# 10_FLASH_BOOT.net
KiCad netlist of a schematic drawn in Altium Designer
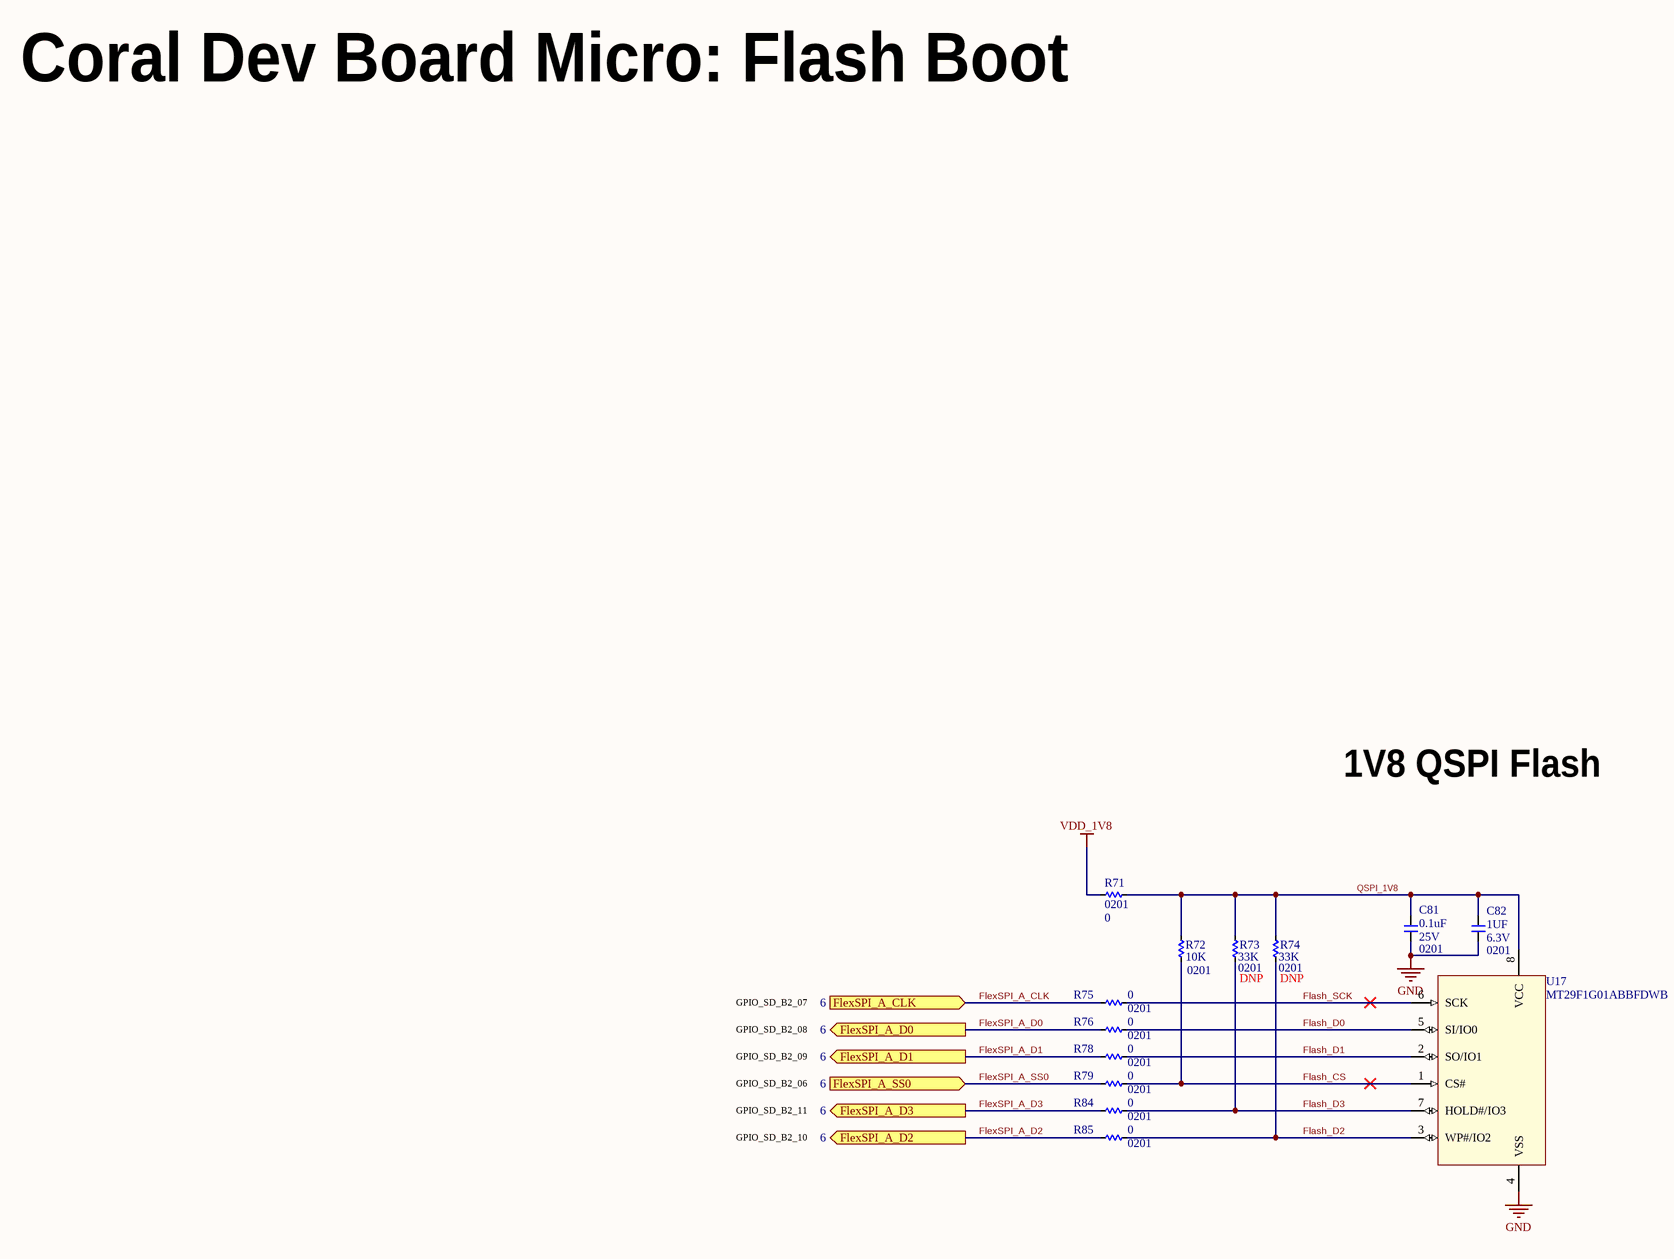
[diagram p0: 10 FLASH_BOOT.SchDoc]

(export (version "E")
  (design (tool "Eeschema 10.0.6"))
  (components
    (comp (ref "C81")
      (value "0.1uF")
      (footprint "C0201Y")
      (description "CAP, CER, X5R, 0.1uF, 25V, 20%, 0201, 0.33mm T")
      (fields
        (field (name "MFG") "MURATA")
        (field (name "PACKAGE") "0201")
        (field (name "VOLTAGE") "25V")
        (field (name "TOLERANCE") "20%")
      )
      (libsource (lib "AltiumReleaseLibDB") (part "__Template_Cap"))
    )
    (comp (ref "C82")
      (value "1UF")
      (footprint "C0201_H0.39MM")
      (description "CAP, CER, X6S, 1uF, 20%, 6.3V, 0201, 0.39mm")
      (fields
        (field (name "MFG") "MURATA")
        (field (name "PACKAGE") "0201")
        (field (name "VOLTAGE") "6.3V")
        (field (name "TOLERANCE") "20%")
      )
      (libsource (lib "AltiumReleaseLibDB") (part "__Template_Cap"))
    )
    (comp (ref "R71")
      (value "0")
      (footprint "R0201")
      (description "RES, 0.0, 1/20W, 0201")
      (fields (field (name "MFG") "PANASONIC") (field (name "PACKAGE") "0201") (field (name "POWER") "1/20W"))
      (libsource (lib "AltiumReleaseLibDB") (part "__Template_Resistor"))
    )
    (comp (ref "R72")
      (value "10K")
      (footprint "R0201")
      (description "RES, 10K, 1%, 1/20W, 0201")
      (fields (field (name "MFG") "YAGEO") (field (name "PACKAGE") "0201") (field (name "POWER") "1/20W"))
      (libsource (lib "AltiumReleaseLibDB") (part "__Template_Resistor"))
    )
    (comp (ref "R73")
      (value "33K")
      (footprint "R0201")
      (description "RES, 33K, 1%, 1/20W, 0201")
      (fields
        (field (name "MFG") "YAGEO")
        (field (name "PACKAGE") "0201")
        (field (name "POWER") "1/20W")
        (field (name "DNP") "DNP")
      )
      (libsource (lib "AltiumReleaseLibDB") (part "__Template_Resistor"))
    )
    (comp (ref "R74")
      (value "33K")
      (footprint "R0201")
      (description "RES, 33K, 1%, 1/20W, 0201")
      (fields
        (field (name "MFG") "YAGEO")
        (field (name "PACKAGE") "0201")
        (field (name "POWER") "1/20W")
        (field (name "DNP") "DNP")
      )
      (libsource (lib "AltiumReleaseLibDB") (part "__Template_Resistor"))
    )
    (comp (ref "R75")
      (value "0")
      (footprint "R0201")
      (description "RES, 0.0, 1/20W, 0201")
      (fields (field (name "MFG") "PANASONIC") (field (name "PACKAGE") "0201") (field (name "POWER") "1/20W"))
      (libsource (lib "AltiumReleaseLibDB") (part "__Template_Resistor"))
    )
    (comp (ref "R76")
      (value "0")
      (footprint "R0201")
      (description "RES, 0.0, 1/20W, 0201")
      (fields (field (name "MFG") "PANASONIC") (field (name "PACKAGE") "0201") (field (name "POWER") "1/20W"))
      (libsource (lib "AltiumReleaseLibDB") (part "__Template_Resistor"))
    )
    (comp (ref "R78")
      (value "0")
      (footprint "R0201")
      (description "RES, 0.0, 1/20W, 0201")
      (fields (field (name "MFG") "PANASONIC") (field (name "PACKAGE") "0201") (field (name "POWER") "1/20W"))
      (libsource (lib "AltiumReleaseLibDB") (part "__Template_Resistor"))
    )
    (comp (ref "R79")
      (value "0")
      (footprint "R0201")
      (description "RES, 0.0, 1/20W, 0201")
      (fields (field (name "MFG") "PANASONIC") (field (name "PACKAGE") "0201") (field (name "POWER") "1/20W"))
      (libsource (lib "AltiumReleaseLibDB") (part "__Template_Resistor"))
    )
    (comp (ref "R84")
      (value "0")
      (footprint "R0201")
      (description "RES, 0.0, 1/20W, 0201")
      (fields (field (name "MFG") "PANASONIC") (field (name "PACKAGE") "0201") (field (name "POWER") "1/20W"))
      (libsource (lib "AltiumReleaseLibDB") (part "__Template_Resistor"))
    )
    (comp (ref "R85")
      (value "0")
      (footprint "R0201")
      (description "RES, 0.0, 1/20W, 0201")
      (fields (field (name "MFG") "PANASONIC") (field (name "PACKAGE") "0201") (field (name "POWER") "1/20W"))
      (libsource (lib "AltiumReleaseLibDB") (part "__Template_Resistor"))
    )
    (comp (ref "U17")
      (value "FLASH_MT29F1G01ABBFDWB")
      (footprint "UDFN800X600X65-8")
      (description "IC, MEMORY, MT29F1G01ABB, NON-VOLATILE, FLASH, 1Gb(1G x 1), SPI, 1.7 TO 1.95V VIN, UDFN-8")
      (fields (field (name "MFG") "Micron Technology Inc.") (field (name "MFG P/N") "MT29F1G01ABBFDWB"))
      (libsource (lib "AltiumReleaseLibDB") (part "FLASH_MT29F1G01ABBFDWB"))
    )
  )
  (nets
    (net (code "1") (name "/Flash_CS") (class "Default")
      (node (ref "R72") (pin "1") (pintype "passive"))
      (node (ref "R79") (pin "2") (pintype "passive"))
      (node (ref "U17") (pin "1") (pinfunction "CS#_1") (pintype "input"))
    )
    (net (code "2") (name "/Flash_D0") (class "Default")
      (node (ref "R76") (pin "2") (pintype "passive"))
      (node (ref "U17") (pin "5") (pinfunction "SI/IO0_5") (pintype "bidirectional"))
    )
    (net (code "3") (name "/Flash_D1") (class "Default")
      (node (ref "R78") (pin "2") (pintype "passive"))
      (node (ref "U17") (pin "2") (pinfunction "SO/IO1_2") (pintype "bidirectional"))
    )
    (net (code "4") (name "/Flash_D2") (class "Default")
      (node (ref "R74") (pin "1") (pintype "passive"))
      (node (ref "R85") (pin "2") (pintype "passive"))
      (node (ref "U17") (pin "3") (pinfunction "WP#/IO2_3") (pintype "bidirectional"))
    )
    (net (code "5") (name "/Flash_D3") (class "Default")
      (node (ref "R73") (pin "1") (pintype "passive"))
      (node (ref "R84") (pin "2") (pintype "passive"))
      (node (ref "U17") (pin "7") (pinfunction "HOLD#/IO3_7") (pintype "bidirectional"))
    )
    (net (code "6") (name "/Flash_SCK") (class "Default")
      (node (ref "R75") (pin "2") (pintype "passive"))
      (node (ref "U17") (pin "6") (pinfunction "SCK_6") (pintype "input"))
    )
    (net (code "7") (name "/FlexSPI_A_CLK") (class "Default")
      (node (ref "R75") (pin "1") (pintype "passive"))
    )
    (net (code "8") (name "/FlexSPI_A_D0") (class "Default") (node (ref "R76") (pin "1") (pintype "passive")))
    (net (code "9") (name "/FlexSPI_A_D1") (class "Default") (node (ref "R78") (pin "1") (pintype "passive")))
    (net (code "10") (name "/FlexSPI_A_D2") (class "Default")
      (node (ref "R85") (pin "1") (pintype "passive"))
    )
    (net (code "11") (name "/FlexSPI_A_D3") (class "Default")
      (node (ref "R84") (pin "1") (pintype "passive"))
    )
    (net (code "12") (name "/FlexSPI_A_SS0") (class "Default")
      (node (ref "R79") (pin "1") (pintype "passive"))
    )
    (net (code "13") (name "/QSPI_1V8") (class "Default")
      (node (ref "C81") (pin "1") (pintype "passive"))
      (node (ref "C82") (pin "1") (pintype "passive"))
      (node (ref "R71") (pin "1") (pintype "passive"))
      (node (ref "R72") (pin "2") (pintype "passive"))
      (node (ref "R73") (pin "2") (pintype "passive"))
      (node (ref "R74") (pin "2") (pintype "passive"))
      (node (ref "U17") (pin "8") (pinfunction "VCC_8") (pintype "power_in"))
    )
    (net (code "14") (name "GND") (class "Default")
      (node (ref "C81") (pin "2") (pintype "passive"))
      (node (ref "C82") (pin "2") (pintype "passive"))
      (node (ref "U17") (pin "4") (pinfunction "VSS_4") (pintype "power_in"))
    )
    (net (code "15") (name "VDD_1V8") (class "Default") (node (ref "R71") (pin "2") (pintype "passive")))
  )
)
